# e-box.net
KiCad netlist of a schematic drawn in EAGLE
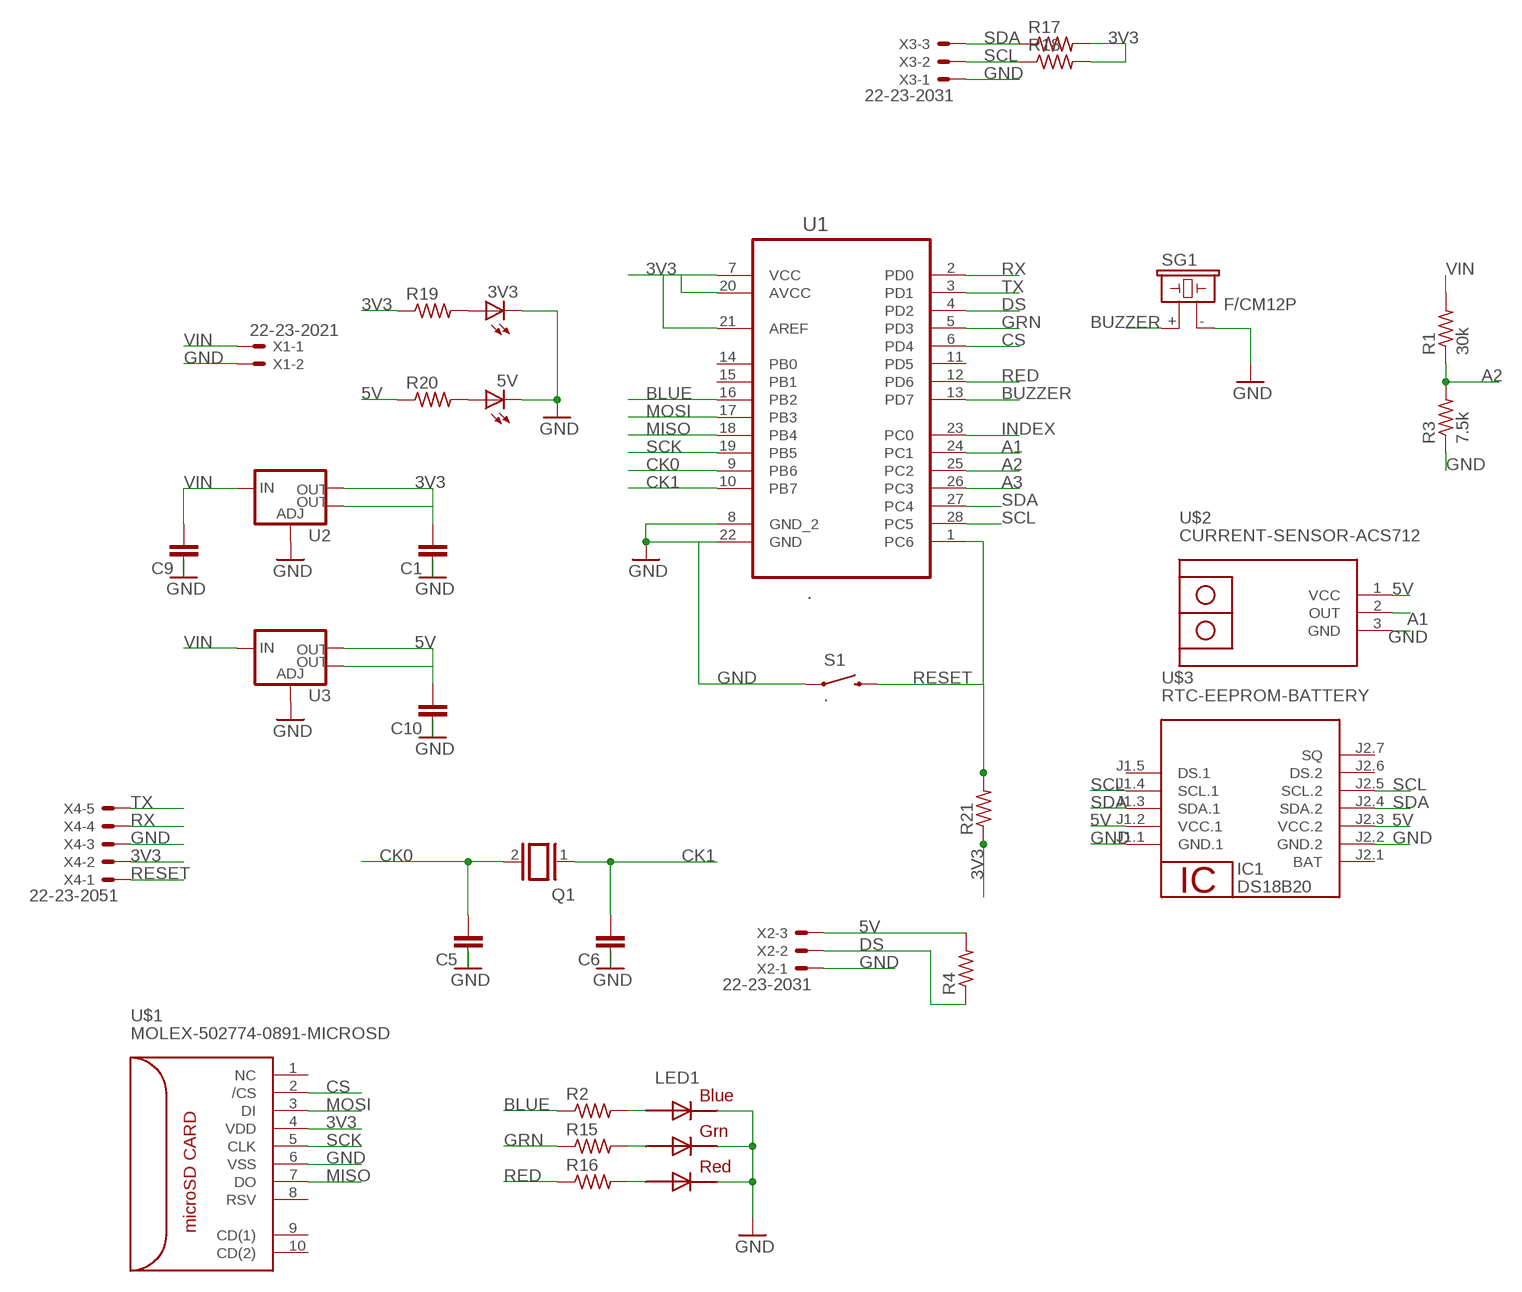
[diagram p0: schematic, sheet 1]

(export (version "E")
  (design (tool "Eeschema 10.0.6"))
  (components
    (comp (ref "3V3")
      (value "LEDSMT1206")
      (footprint "eagle-import:1206")
      (libsource (lib "eagle-import") (part "LEDSMT1206"))
    )
    (comp (ref "5V")
      (value "LEDSMT1206")
      (footprint "eagle-import:1206")
      (libsource (lib "eagle-import") (part "LEDSMT1206"))
    )
    (comp (ref "C1")
      (value "10UF-1210-50V-20%")
      (footprint "eagle-import:1210")
      (libsource (lib "eagle-import") (part "10UF-1210-50V-20%"))
    )
    (comp (ref "C5")
      (value "10UF-1210-50V-20%")
      (footprint "eagle-import:1210")
      (libsource (lib "eagle-import") (part "10UF-1210-50V-20%"))
    )
    (comp (ref "C6")
      (value "10UF-1210-50V-20%")
      (footprint "eagle-import:1210")
      (libsource (lib "eagle-import") (part "10UF-1210-50V-20%"))
    )
    (comp (ref "C9")
      (value "10UF-1210-50V-20%")
      (footprint "eagle-import:1210")
      (libsource (lib "eagle-import") (part "10UF-1210-50V-20%"))
    )
    (comp (ref "C10")
      (value "10UF-1210-50V-20%")
      (footprint "eagle-import:1210")
      (libsource (lib "eagle-import") (part "10UF-1210-50V-20%"))
    )
    (comp (ref "IC1")
      (value "DS18B20")
      (footprint "eagle-import:TO92-")
      (libsource (lib "eagle-import") (part "DS18B20"))
    )
    (comp (ref "LED1")
      (value ".")
      (footprint "eagle-import:RGBLED5050")
      (libsource (lib "eagle-import") (part "RGBLED5050"))
    )
    (comp (ref "Q1")
      (value "XTAL/S")
      (footprint "eagle-import:QS")
      (libsource (lib "eagle-import") (part "XTAL/S"))
    )
    (comp (ref "R1")
      (value "30k")
      (footprint "eagle-import:M1206")
      (libsource (lib "eagle-import") (part "R-US_M1206"))
    )
    (comp (ref "R2")
      (value "R-US_M1206")
      (footprint "eagle-import:M1206")
      (libsource (lib "eagle-import") (part "R-US_M1206"))
    )
    (comp (ref "R3")
      (value "7.5k")
      (footprint "eagle-import:M1206")
      (libsource (lib "eagle-import") (part "R-US_M1206"))
    )
    (comp (ref "R4")
      (value "R-US_M1206")
      (footprint "eagle-import:M1206")
      (libsource (lib "eagle-import") (part "R-US_M1206"))
    )
    (comp (ref "R15")
      (value "R-US_M1206")
      (footprint "eagle-import:M1206")
      (libsource (lib "eagle-import") (part "R-US_M1206"))
    )
    (comp (ref "R16")
      (value "R-US_M1206")
      (footprint "eagle-import:M1206")
      (libsource (lib "eagle-import") (part "R-US_M1206"))
    )
    (comp (ref "R17")
      (value "R-US_M1206")
      (footprint "eagle-import:M1206")
      (libsource (lib "eagle-import") (part "R-US_M1206"))
    )
    (comp (ref "R18")
      (value "R-US_M1206")
      (footprint "eagle-import:M1206")
      (libsource (lib "eagle-import") (part "R-US_M1206"))
    )
    (comp (ref "R19")
      (value "R-US_M1206")
      (footprint "eagle-import:M1206")
      (libsource (lib "eagle-import") (part "R-US_M1206"))
    )
    (comp (ref "R20")
      (value "R-US_M1206")
      (footprint "eagle-import:M1206")
      (libsource (lib "eagle-import") (part "R-US_M1206"))
    )
    (comp (ref "R21")
      (value "R-US_M1206")
      (footprint "eagle-import:M1206")
      (libsource (lib "eagle-import") (part "R-US_M1206"))
    )
    (comp (ref "S1")
      (value ".")
      (footprint "eagle-import:TACTILE-SWITCH-1101NE")
      (libsource (lib "eagle-import") (part "SWITCH-MOMENTARY-2SMD-1101NE"))
    )
    (comp (ref "SG1")
      (value "F/CM12P")
      (footprint "eagle-import:F_CM12P")
      (libsource (lib "eagle-import") (part "F/CM12P"))
    )
    (comp (ref "U$1")
      (value "MOLEX-502774-0891-MICROSD")
      (footprint "eagle-import:MOLEX-502774-0891-MICROSD")
      (libsource (lib "eagle-import") (part "MOLEX-502774-0891-MICROSD"))
    )
    (comp (ref "U$2")
      (value "CURRENT-SENSOR-ACS712")
      (footprint "eagle-import:CURRENT-SENSOR-ACS712")
      (libsource (lib "eagle-import") (part "CURRENT-SENSOR-ACS712"))
    )
    (comp (ref "U$3")
      (value "RTC-EEPROM-BATTERY")
      (footprint "eagle-import:RTC-EEPROM-BATTERY")
      (libsource (lib "eagle-import") (part "RTC-EEPROM-BATTERY"))
    )
    (comp (ref "U1")
      (value ".")
      (footprint "eagle-import:DIP254P762X457-28")
      (fields (field (name "MPN") "ATMEGA328P-PU"))
      (libsource (lib "eagle-import") (part "ATMEGA328P-PU"))
    )
    (comp (ref "U2")
      (value "V_REG_LM1117SOT223")
      (footprint "eagle-import:SOT223")
      (libsource (lib "eagle-import") (part "V_REG_LM1117SOT223"))
    )
    (comp (ref "U3")
      (value "V_REG_LM1117SOT223")
      (footprint "eagle-import:SOT223")
      (libsource (lib "eagle-import") (part "V_REG_LM1117SOT223"))
    )
    (comp (ref "X1")
      (value "22-23-2021")
      (footprint "eagle-import:22-23-2021")
      (fields (field (name "MF") "MOLEX"))
      (libsource (lib "eagle-import") (part "22-23-2021"))
    )
    (comp (ref "X2")
      (value "22-23-2031")
      (footprint "eagle-import:22-23-2031")
      (fields (field (name "MF") "MOLEX"))
      (libsource (lib "eagle-import") (part "22-23-2031"))
    )
    (comp (ref "X3")
      (value "22-23-2031")
      (footprint "eagle-import:22-23-2031")
      (fields (field (name "MF") "MOLEX"))
      (libsource (lib "eagle-import") (part "22-23-2031"))
    )
    (comp (ref "X4")
      (value "22-23-2051")
      (footprint "eagle-import:22-23-2051")
      (fields (field (name "MF") "MOLEX"))
      (libsource (lib "eagle-import") (part "22-23-2051"))
    )
  )
  (nets
    (net (code "1") (name "/3V3") (class "Default")
      (node (ref "C1") (pin "2") (pinfunction "2_2") (pintype "passive"))
      (node (ref "R17") (pin "2") (pinfunction "2_2") (pintype "passive"))
      (node (ref "R18") (pin "2") (pinfunction "2_2") (pintype "passive"))
      (node (ref "R19") (pin "1") (pinfunction "1_1") (pintype "passive"))
      (node (ref "R21") (pin "1") (pinfunction "1_1") (pintype "passive"))
      (node (ref "U$1") (pin "4") (pinfunction "VDD_4") (pintype "bidirectional"))
      (node (ref "U1") (pin "20") (pinfunction "AVCC_20") (pintype "power_in"))
      (node (ref "U1") (pin "21") (pinfunction "AREF_21") (pintype "input"))
      (node (ref "U1") (pin "7") (pinfunction "VCC_7") (pintype "power_in"))
      (node (ref "U2") (pin "2") (pinfunction "OUT_2") (pintype "output"))
      (node (ref "U2") (pin "4") (pinfunction "OUT_4") (pintype "output"))
      (node (ref "X4") (pin "2") (pinfunction "S_2") (pintype "passive"))
    )
    (net (code "2") (name "/5V") (class "Default")
      (node (ref "C10") (pin "2") (pinfunction "2_2") (pintype "passive"))
      (node (ref "R20") (pin "1") (pinfunction "1_1") (pintype "passive"))
      (node (ref "R4") (pin "2") (pinfunction "2_2") (pintype "passive"))
      (node (ref "U$2") (pin "1") (pinfunction "VCC_1") (pintype "power_in"))
      (node (ref "U$3") (pin "J1.2") (pinfunction "VCC.1_J1.2") (pintype "power_in"))
      (node (ref "U$3") (pin "J2.3") (pinfunction "VCC.2_J2.3") (pintype "power_in"))
      (node (ref "U3") (pin "2") (pinfunction "OUT_2") (pintype "output"))
      (node (ref "U3") (pin "4") (pinfunction "OUT_4") (pintype "output"))
      (node (ref "X2") (pin "3") (pinfunction "S_3") (pintype "passive"))
    )
    (net (code "3") (name "/A1") (class "Default")
      (node (ref "U$2") (pin "2") (pinfunction "OUT_2") (pintype "output"))
      (node (ref "U1") (pin "24") (pinfunction "PC1_24") (pintype "bidirectional"))
    )
    (net (code "4") (name "/A2") (class "Default")
      (node (ref "R1") (pin "1") (pinfunction "1_1") (pintype "passive"))
      (node (ref "R3") (pin "2") (pinfunction "2_2") (pintype "passive"))
      (node (ref "U1") (pin "25") (pinfunction "PC2_25") (pintype "bidirectional"))
    )
    (net (code "5") (name "/A3") (class "Default")
      (node (ref "U1") (pin "26") (pinfunction "PC3_26") (pintype "bidirectional"))
    )
    (net (code "6") (name "/BLUE") (class "Default")
      (node (ref "R2") (pin "1") (pinfunction "1_1") (pintype "passive"))
      (node (ref "U1") (pin "16") (pinfunction "PB2_16") (pintype "bidirectional"))
    )
    (net (code "7") (name "/BUZZER") (class "Default")
      (node (ref "SG1") (pin "+") (pinfunction "1_+") (pintype "passive"))
      (node (ref "U1") (pin "13") (pinfunction "PD7_13") (pintype "bidirectional"))
    )
    (net (code "8") (name "/CK0") (class "Default")
      (node (ref "C5") (pin "2") (pinfunction "2_2") (pintype "passive"))
      (node (ref "Q1") (pin "2") (pinfunction "2_2") (pintype "passive"))
      (node (ref "U1") (pin "9") (pinfunction "PB6_9") (pintype "bidirectional"))
    )
    (net (code "9") (name "/CK1") (class "Default")
      (node (ref "C6") (pin "2") (pinfunction "2_2") (pintype "passive"))
      (node (ref "Q1") (pin "1") (pinfunction "1_1") (pintype "passive"))
      (node (ref "U1") (pin "10") (pinfunction "PB7_10") (pintype "bidirectional"))
    )
    (net (code "10") (name "/CS") (class "Default")
      (node (ref "U$1") (pin "2") (pinfunction "/CS_2") (pintype "bidirectional"))
      (node (ref "U1") (pin "6") (pinfunction "PD4_6") (pintype "bidirectional"))
    )
    (net (code "11") (name "/DS") (class "Default")
      (node (ref "R4") (pin "1") (pinfunction "1_1") (pintype "passive"))
      (node (ref "U1") (pin "4") (pinfunction "PD2_4") (pintype "bidirectional"))
      (node (ref "X2") (pin "2") (pinfunction "S_2") (pintype "passive"))
    )
    (net (code "12") (name "/GRN") (class "Default")
      (node (ref "R15") (pin "1") (pinfunction "1_1") (pintype "passive"))
      (node (ref "U1") (pin "5") (pinfunction "PD3_5") (pintype "bidirectional"))
    )
    (net (code "13") (name "/INDEX") (class "Default")
      (node (ref "U1") (pin "23") (pinfunction "PC0_23") (pintype "bidirectional"))
    )
    (net (code "14") (name "/MISO") (class "Default")
      (node (ref "U$1") (pin "7") (pinfunction "DO_7") (pintype "bidirectional"))
      (node (ref "U1") (pin "18") (pinfunction "PB4_18") (pintype "bidirectional"))
    )
    (net (code "15") (name "/MOSI") (class "Default")
      (node (ref "U$1") (pin "3") (pinfunction "DI_3") (pintype "bidirectional"))
      (node (ref "U1") (pin "17") (pinfunction "PB3_17") (pintype "bidirectional"))
    )
    (net (code "16") (name "/RED") (class "Default")
      (node (ref "R16") (pin "1") (pinfunction "1_1") (pintype "passive"))
      (node (ref "U1") (pin "12") (pinfunction "PD6_12") (pintype "bidirectional"))
    )
    (net (code "17") (name "/RESET") (class "Default")
      (node (ref "R21") (pin "2") (pinfunction "2_2") (pintype "passive"))
      (node (ref "S1") (pin "2") (pinfunction "2_2") (pintype "passive"))
      (node (ref "U1") (pin "1") (pinfunction "PC6_1") (pintype "bidirectional"))
      (node (ref "X4") (pin "1") (pinfunction "S_1") (pintype "passive"))
    )
    (net (code "18") (name "/RX") (class "Default")
      (node (ref "U1") (pin "2") (pinfunction "PD0_2") (pintype "bidirectional"))
      (node (ref "X4") (pin "4") (pinfunction "S_4") (pintype "passive"))
    )
    (net (code "19") (name "/SCK") (class "Default")
      (node (ref "U$1") (pin "5") (pinfunction "CLK_5") (pintype "bidirectional"))
      (node (ref "U1") (pin "19") (pinfunction "PB5_19") (pintype "bidirectional"))
    )
    (net (code "20") (name "/SCL") (class "Default")
      (node (ref "R18") (pin "1") (pinfunction "1_1") (pintype "passive"))
      (node (ref "U$3") (pin "J1.4") (pinfunction "SCL.1_J1.4") (pintype "bidirectional"))
      (node (ref "U$3") (pin "J2.5") (pinfunction "SCL.2_J2.5") (pintype "bidirectional"))
      (node (ref "U1") (pin "28") (pinfunction "PC5_28") (pintype "bidirectional"))
      (node (ref "X3") (pin "2") (pinfunction "S_2") (pintype "passive"))
    )
    (net (code "21") (name "/SDA") (class "Default")
      (node (ref "R17") (pin "1") (pinfunction "1_1") (pintype "passive"))
      (node (ref "U$3") (pin "J1.3") (pinfunction "SDA.1_J1.3") (pintype "bidirectional"))
      (node (ref "U$3") (pin "J2.4") (pinfunction "SDA.2_J2.4") (pintype "bidirectional"))
      (node (ref "U1") (pin "27") (pinfunction "PC4_27") (pintype "bidirectional"))
      (node (ref "X3") (pin "3") (pinfunction "S_3") (pintype "passive"))
    )
    (net (code "22") (name "/TX") (class "Default")
      (node (ref "U1") (pin "3") (pinfunction "PD1_3") (pintype "bidirectional"))
      (node (ref "X4") (pin "5") (pinfunction "S_5") (pintype "passive"))
    )
    (net (code "23") (name "/VIN") (class "Default")
      (node (ref "C9") (pin "2") (pinfunction "2_2") (pintype "passive"))
      (node (ref "R1") (pin "2") (pinfunction "2_2") (pintype "passive"))
      (node (ref "U2") (pin "3") (pinfunction "IN_3") (pintype "input"))
      (node (ref "U3") (pin "3") (pinfunction "IN_3") (pintype "input"))
      (node (ref "X1") (pin "1") (pinfunction "S_1") (pintype "passive"))
    )
    (net (code "24") (name "GND") (class "Default")
      (node (ref "3V3") (pin "C") (pinfunction "C_C") (pintype "passive"))
      (node (ref "5V") (pin "C") (pinfunction "C_C") (pintype "passive"))
      (node (ref "C1") (pin "1") (pinfunction "1_1") (pintype "passive"))
      (node (ref "C10") (pin "1") (pinfunction "1_1") (pintype "passive"))
      (node (ref "C5") (pin "1") (pinfunction "1_1") (pintype "passive"))
      (node (ref "C6") (pin "1") (pinfunction "1_1") (pintype "passive"))
      (node (ref "C9") (pin "1") (pinfunction "1_1") (pintype "passive"))
      (node (ref "LED1") (pin "4") (pinfunction "BLUE_C_4") (pintype "bidirectional"))
      (node (ref "LED1") (pin "5") (pinfunction "RED_C_5") (pintype "bidirectional"))
      (node (ref "LED1") (pin "6") (pinfunction "GREEN_C_6") (pintype "bidirectional"))
      (node (ref "R3") (pin "1") (pinfunction "1_1") (pintype "passive"))
      (node (ref "S1") (pin "1") (pinfunction "1_1") (pintype "passive"))
      (node (ref "SG1") (pin "-") (pinfunction "2_-") (pintype "passive"))
      (node (ref "U$1") (pin "6") (pinfunction "VSS_6") (pintype "bidirectional"))
      (node (ref "U$2") (pin "3") (pinfunction "GND_3") (pintype "power_in"))
      (node (ref "U$3") (pin "J1.1") (pinfunction "GND.1_J1.1") (pintype "power_in"))
      (node (ref "U$3") (pin "J2.2") (pinfunction "GND.2_J2.2") (pintype "power_in"))
      (node (ref "U1") (pin "22") (pinfunction "GND_22") (pintype "passive"))
      (node (ref "U1") (pin "8") (pinfunction "GND_2_8") (pintype "passive"))
      (node (ref "U2") (pin "1") (pinfunction "ADJ_1") (pintype "input"))
      (node (ref "U3") (pin "1") (pinfunction "ADJ_1") (pintype "input"))
      (node (ref "X1") (pin "2") (pinfunction "S_2") (pintype "passive"))
      (node (ref "X2") (pin "1") (pinfunction "S_1") (pintype "passive"))
      (node (ref "X3") (pin "1") (pinfunction "S_1") (pintype "passive"))
      (node (ref "X4") (pin "3") (pinfunction "S_3") (pintype "passive"))
    )
    (net (code "25") (name "Net-(3V3-PadA)") (class "Default")
      (node (ref "3V3") (pin "A") (pinfunction "A_A") (pintype "passive"))
      (node (ref "R19") (pin "2") (pinfunction "2_2") (pintype "passive"))
    )
    (net (code "26") (name "Net-(5V-PadA)") (class "Default")
      (node (ref "5V") (pin "A") (pinfunction "A_A") (pintype "passive"))
      (node (ref "R20") (pin "2") (pinfunction "2_2") (pintype "passive"))
    )
    (net (code "27") (name "Net-(LED1-BLUE_A)") (class "Default")
      (node (ref "LED1") (pin "3") (pinfunction "BLUE_A_3") (pintype "bidirectional"))
      (node (ref "R2") (pin "2") (pinfunction "2_2") (pintype "passive"))
    )
    (net (code "28") (name "Net-(LED1-GREEN_A)") (class "Default")
      (node (ref "LED1") (pin "1") (pinfunction "GREEN_A_1") (pintype "bidirectional"))
      (node (ref "R15") (pin "2") (pinfunction "2_2") (pintype "passive"))
    )
    (net (code "29") (name "Net-(LED1-RED_A)") (class "Default")
      (node (ref "LED1") (pin "2") (pinfunction "RED_A_2") (pintype "bidirectional"))
      (node (ref "R16") (pin "2") (pinfunction "2_2") (pintype "passive"))
    )
    (net (code "30") (name "unconnected-(U$1-CD(1)-Pad9)") (class "Default")
      (node (ref "U$1") (pin "9") (pinfunction "CD(1)_9") (pintype "bidirectional"))
    )
    (net (code "31") (name "unconnected-(U$1-CD(2)-Pad10)") (class "Default")
      (node (ref "U$1") (pin "10") (pinfunction "CD(2)_10") (pintype "bidirectional"))
    )
    (net (code "32") (name "unconnected-(U$1-NC-Pad1)") (class "Default")
      (node (ref "U$1") (pin "1") (pinfunction "NC_1") (pintype "bidirectional"))
    )
    (net (code "33") (name "unconnected-(U$1-RSV-Pad8)") (class "Default")
      (node (ref "U$1") (pin "8") (pinfunction "RSV_8") (pintype "bidirectional"))
    )
    (net (code "34") (name "unconnected-(U$3-BAT-PadJ2.1)") (class "Default")
      (node (ref "U$3") (pin "J2.1") (pinfunction "BAT_J2.1") (pintype "bidirectional"))
    )
    (net (code "35") (name "unconnected-(U$3-DS.1-PadJ1.5)") (class "Default")
      (node (ref "U$3") (pin "J1.5") (pinfunction "DS.1_J1.5") (pintype "bidirectional"))
    )
    (net (code "36") (name "unconnected-(U$3-DS.2-PadJ2.6)") (class "Default")
      (node (ref "U$3") (pin "J2.6") (pinfunction "DS.2_J2.6") (pintype "bidirectional"))
    )
    (net (code "37") (name "unconnected-(U$3-SQ-PadJ2.7)") (class "Default")
      (node (ref "U$3") (pin "J2.7") (pinfunction "SQ_J2.7") (pintype "bidirectional"))
    )
    (net (code "38") (name "unconnected-(U1-PB0-Pad14)") (class "Default")
      (node (ref "U1") (pin "14") (pinfunction "PB0_14") (pintype "bidirectional"))
    )
    (net (code "39") (name "unconnected-(U1-PB1-Pad15)") (class "Default")
      (node (ref "U1") (pin "15") (pinfunction "PB1_15") (pintype "bidirectional"))
    )
    (net (code "40") (name "unconnected-(U1-PD5-Pad11)") (class "Default")
      (node (ref "U1") (pin "11") (pinfunction "PD5_11") (pintype "bidirectional"))
    )
  )
)
